# BOTTOM_BRD_v_1_0_4.net
KiCad netlist of a schematic drawn in EAGLE
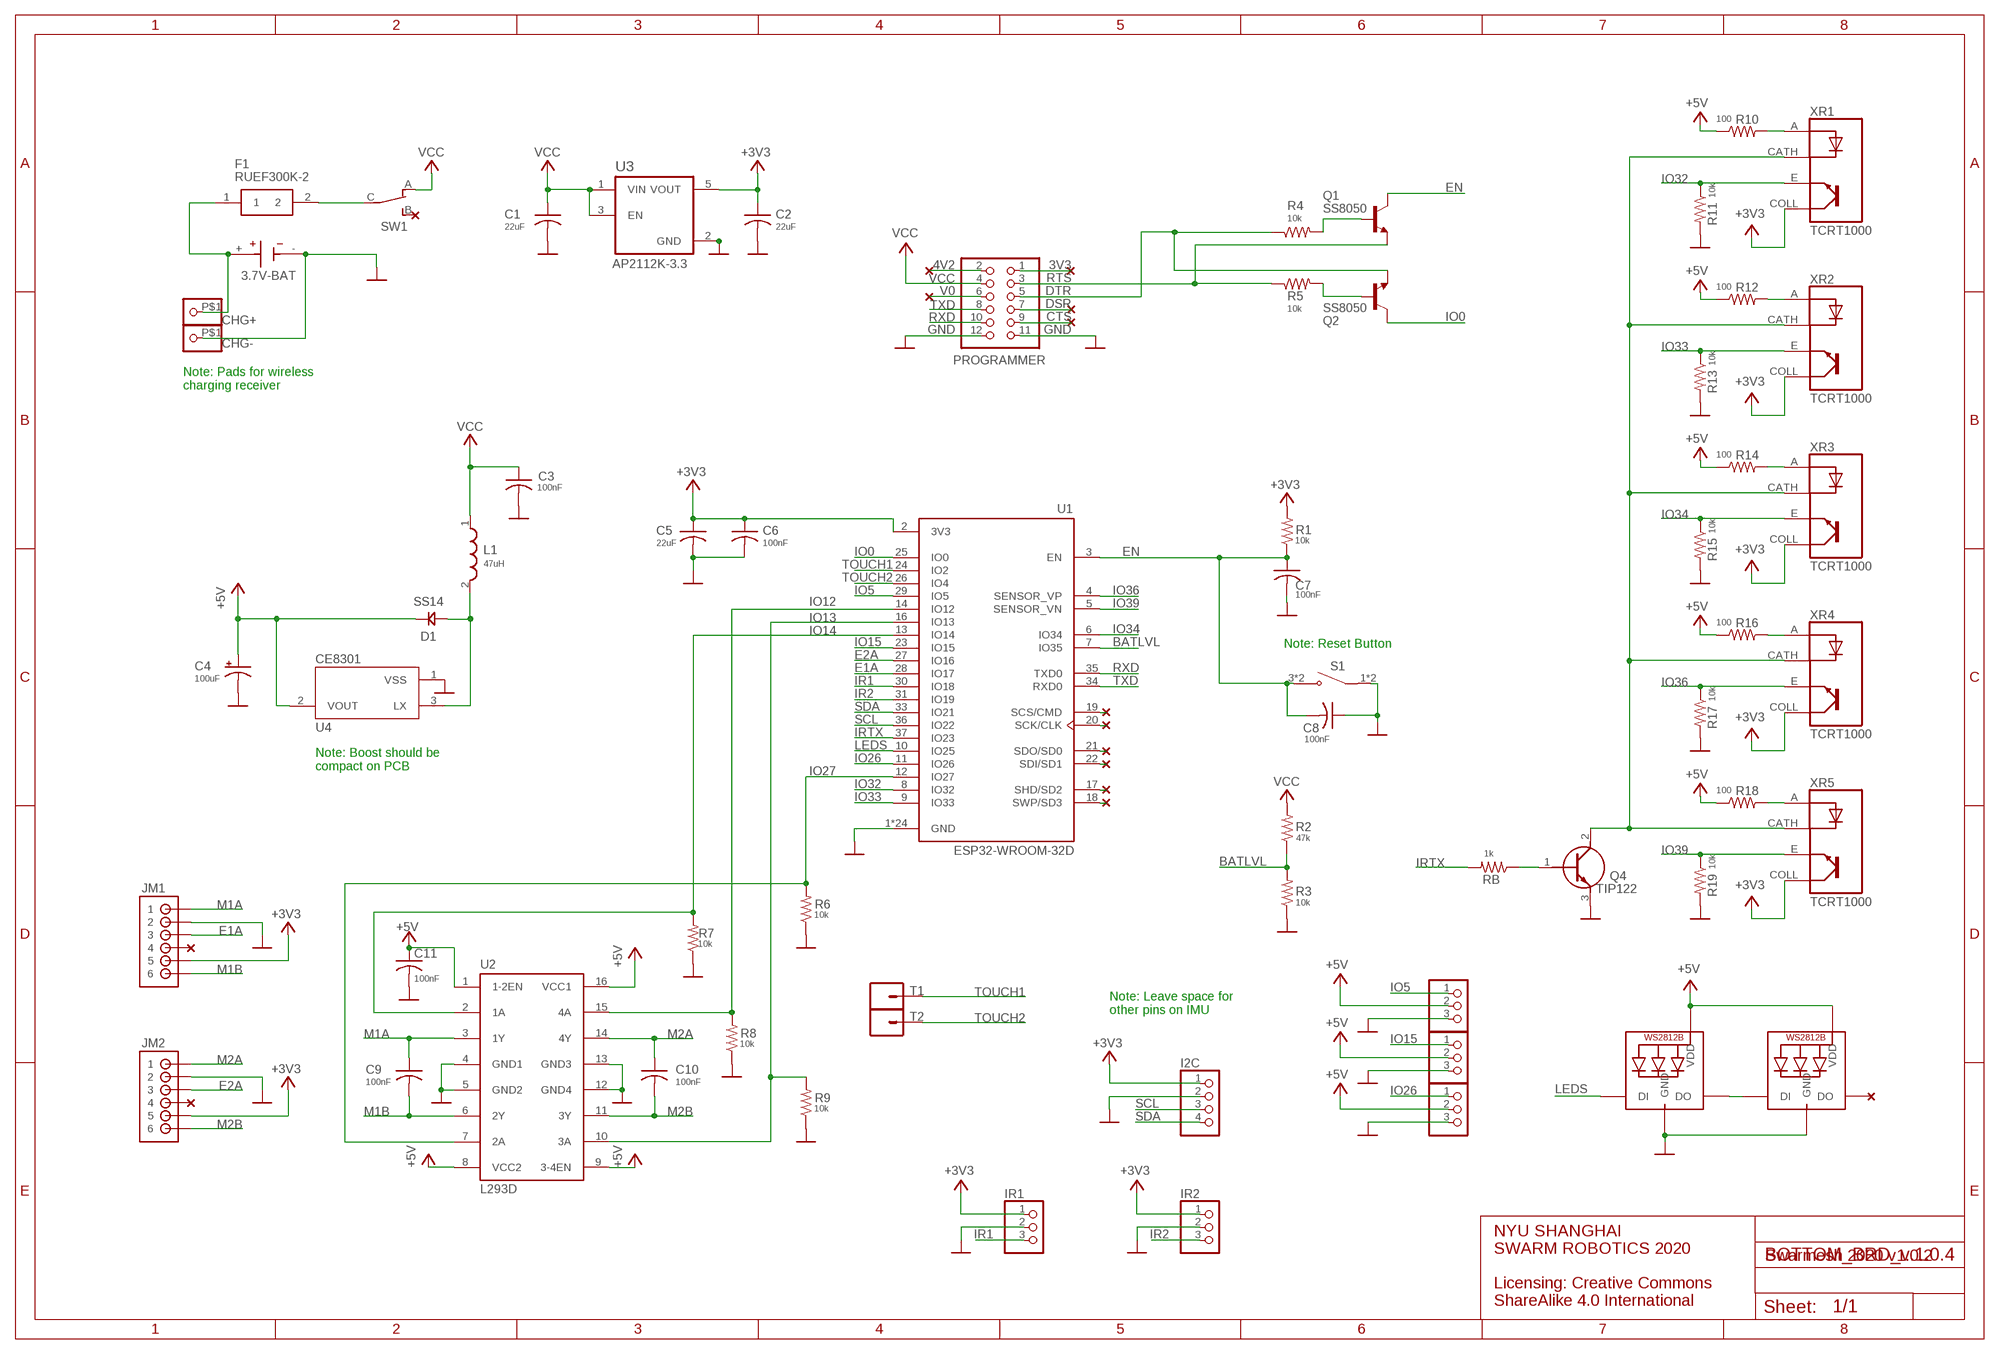
[diagram p0: schematic, sheet 1]

(export (version "E")
  (design (tool "Eeschema 10.0.6"))
  (components
    (comp (ref "BT")
      (value "3.7V-BAT")
      (footprint "eagle-import:BAT_6S-AA")
      (fields (field (name "MF") "MPD") (field (name "MP") "6S-AA"))
      (libsource (lib "eagle-import") (part "6S-AA"))
    )
    (comp (ref "C1")
      (value "22uF")
      (footprint "eagle-import:C0805")
      (libsource (lib "eagle-import") (part "C-USC0805"))
    )
    (comp (ref "C2")
      (value "22uF")
      (footprint "eagle-import:C0805")
      (libsource (lib "eagle-import") (part "C-USC0805"))
    )
    (comp (ref "C3")
      (value "100nF")
      (footprint "eagle-import:C0805")
      (libsource (lib "eagle-import") (part "C-USC0805"))
    )
    (comp (ref "C4")
      (value "100uF")
      (footprint "eagle-import:153CLV-0605")
      (libsource (lib "eagle-import") (part "CPOL-US153CLV-0605"))
    )
    (comp (ref "C5")
      (value "22uF")
      (footprint "eagle-import:C0805")
      (libsource (lib "eagle-import") (part "C-USC0805"))
    )
    (comp (ref "C6")
      (value "100nF")
      (footprint "eagle-import:C0805")
      (libsource (lib "eagle-import") (part "C-USC0805"))
    )
    (comp (ref "C7")
      (value "100nF")
      (footprint "eagle-import:C0805")
      (libsource (lib "eagle-import") (part "C-USC0805"))
    )
    (comp (ref "C8")
      (value "100nF")
      (footprint "eagle-import:C0805")
      (libsource (lib "eagle-import") (part "C-USC0805"))
    )
    (comp (ref "C9")
      (value "100nF")
      (footprint "eagle-import:C0805")
      (libsource (lib "eagle-import") (part "C-USC0805"))
    )
    (comp (ref "C10")
      (value "100nF")
      (footprint "eagle-import:C0805")
      (libsource (lib "eagle-import") (part "C-USC0805"))
    )
    (comp (ref "C11")
      (value "100nF")
      (footprint "eagle-import:C0805")
      (libsource (lib "eagle-import") (part "C-USC0805"))
    )
    (comp (ref "CHARGING")
      (value "WS2812B5050")
      (footprint "eagle-import:WS2812B")
      (libsource (lib "eagle-import") (part "WS2812B5050"))
    )
    (comp (ref "CHG+")
      (value "PINHD-1X1-BIGPOGO")
      (footprint "eagle-import:1X1-BIGPOGO")
      (libsource (lib "eagle-import") (part "PINHD-1X1-BIGPOGO"))
    )
    (comp (ref "CHG-")
      (value "PINHD-1X1-BIGPOGO")
      (footprint "eagle-import:1X1-BIGPOGO")
      (libsource (lib "eagle-import") (part "PINHD-1X1-BIGPOGO"))
    )
    (comp (ref "D1")
      (value "SS14")
      (footprint "eagle-import:DO214")
      (fields (field (name "MF") "ON Semiconductor"))
      (libsource (lib "eagle-import") (part "SS14"))
    )
    (comp (ref "F1")
      (value "RUEF300K-2")
      (footprint "eagle-import:RUEF300K2")
      (libsource (lib "eagle-import") (part "RUEF300K-2"))
    )
    (comp (ref "GPIO5")
      (value "PINHD-1X3")
      (footprint "eagle-import:1X03")
      (libsource (lib "eagle-import") (part "PINHD-1X3"))
    )
    (comp (ref "GPIO15")
      (value "PINHD-1X3")
      (footprint "eagle-import:1X03")
      (libsource (lib "eagle-import") (part "PINHD-1X3"))
    )
    (comp (ref "GPIO26")
      (value "PINHD-1X3")
      (footprint "eagle-import:1X03")
      (libsource (lib "eagle-import") (part "PINHD-1X3"))
    )
    (comp (ref "I2C")
      (value "PINHD-1X4")
      (footprint "eagle-import:1X04")
      (libsource (lib "eagle-import") (part "PINHD-1X4"))
    )
    (comp (ref "IR1")
      (value "PINHD-1X3")
      (footprint "eagle-import:1X03")
      (libsource (lib "eagle-import") (part "PINHD-1X3"))
    )
    (comp (ref "IR2")
      (value "PINHD-1X3")
      (footprint "eagle-import:1X03")
      (libsource (lib "eagle-import") (part "PINHD-1X3"))
    )
    (comp (ref "JM1")
      (value "B6B-ZR")
      (footprint "eagle-import:B6B-ZR")
      (fields (field (name "MF") "JST"))
      (libsource (lib "eagle-import") (part "B6B-ZR"))
    )
    (comp (ref "JM2")
      (value "B6B-ZR")
      (footprint "eagle-import:B6B-ZR")
      (fields (field (name "MF") "JST"))
      (libsource (lib "eagle-import") (part "B6B-ZR"))
    )
    (comp (ref "L1")
      (value "47uH")
      (footprint "eagle-import:INDP5858X480N")
      (fields (field (name "MF") "Bourns") (field (name "MP") "SDR0604-100KL"))
      (libsource (lib "eagle-import") (part "SDR0604-100KL"))
    )
    (comp (ref "PROGRAMMER")
      (value "PINHD-2X6")
      (footprint "eagle-import:2X06")
      (libsource (lib "eagle-import") (part "PINHD-2X6"))
    )
    (comp (ref "Q1")
      (value "SS8050")
      (footprint "eagle-import:SOT23")
      (libsource (lib "eagle-import") (part "BC850"))
    )
    (comp (ref "Q2")
      (value "SS8050")
      (footprint "eagle-import:SOT23")
      (libsource (lib "eagle-import") (part "BC850"))
    )
    (comp (ref "Q4")
      (value "TIP122")
      (footprint "eagle-import:TO270P460X1020X2008-3P")
      (fields (field (name "MOUSER_PART_NUMBER") "511-TIP122"))
      (libsource (lib "eagle-import") (part "TIP122"))
    )
    (comp (ref "R1")
      (value "10k")
      (footprint "eagle-import:M0805")
      (libsource (lib "eagle-import") (part "R-US_M0805"))
    )
    (comp (ref "R2")
      (value "47k")
      (footprint "eagle-import:M0805")
      (libsource (lib "eagle-import") (part "R-US_M0805"))
    )
    (comp (ref "R3")
      (value "10k")
      (footprint "eagle-import:M0805")
      (libsource (lib "eagle-import") (part "R-US_M0805"))
    )
    (comp (ref "R4")
      (value "10k")
      (footprint "eagle-import:M0805")
      (libsource (lib "eagle-import") (part "R-US_M0805"))
    )
    (comp (ref "R5")
      (value "10k")
      (footprint "eagle-import:M0805")
      (libsource (lib "eagle-import") (part "R-US_M0805"))
    )
    (comp (ref "R6")
      (value "10k")
      (footprint "eagle-import:M0805")
      (libsource (lib "eagle-import") (part "R-US_M0805"))
    )
    (comp (ref "R7")
      (value "10k")
      (footprint "eagle-import:M0805")
      (libsource (lib "eagle-import") (part "R-US_M0805"))
    )
    (comp (ref "R8")
      (value "10k")
      (footprint "eagle-import:M0805")
      (libsource (lib "eagle-import") (part "R-US_M0805"))
    )
    (comp (ref "R9")
      (value "10k")
      (footprint "eagle-import:M0805")
      (libsource (lib "eagle-import") (part "R-US_M0805"))
    )
    (comp (ref "R10")
      (value "100")
      (footprint "eagle-import:M0805")
      (libsource (lib "eagle-import") (part "R-US_M0805"))
    )
    (comp (ref "R11")
      (value "10k")
      (footprint "eagle-import:M0805")
      (libsource (lib "eagle-import") (part "R-US_M0805"))
    )
    (comp (ref "R12")
      (value "100")
      (footprint "eagle-import:M0805")
      (libsource (lib "eagle-import") (part "R-US_M0805"))
    )
    (comp (ref "R13")
      (value "10k")
      (footprint "eagle-import:M0805")
      (libsource (lib "eagle-import") (part "R-US_M0805"))
    )
    (comp (ref "R14")
      (value "100")
      (footprint "eagle-import:M0805")
      (libsource (lib "eagle-import") (part "R-US_M0805"))
    )
    (comp (ref "R15")
      (value "10k")
      (footprint "eagle-import:M0805")
      (libsource (lib "eagle-import") (part "R-US_M0805"))
    )
    (comp (ref "R16")
      (value "100")
      (footprint "eagle-import:M0805")
      (libsource (lib "eagle-import") (part "R-US_M0805"))
    )
    (comp (ref "R17")
      (value "10k")
      (footprint "eagle-import:M0805")
      (libsource (lib "eagle-import") (part "R-US_M0805"))
    )
    (comp (ref "R18")
      (value "100")
      (footprint "eagle-import:M0805")
      (libsource (lib "eagle-import") (part "R-US_M0805"))
    )
    (comp (ref "R19")
      (value "10k")
      (footprint "eagle-import:M0805")
      (libsource (lib "eagle-import") (part "R-US_M0805"))
    )
    (comp (ref "RB")
      (value "1k")
      (footprint "eagle-import:M0805")
      (libsource (lib "eagle-import") (part "R-US_M0805"))
    )
    (comp (ref "S1")
      (value "2-1437565-9")
      (footprint "eagle-import:SW_2-1437565-9")
      (fields (field (name "MF") "TE Connectivity"))
      (libsource (lib "eagle-import") (part "2-1437565-9"))
    )
    (comp (ref "STATE")
      (value "WS2812B5050")
      (footprint "eagle-import:WS2812B")
      (libsource (lib "eagle-import") (part "WS2812B5050"))
    )
    (comp (ref "SW1")
      (value "CS12ANW03")
      (footprint "eagle-import:CS12ANW03")
      (fields (field (name "MF") "NKK Switches"))
      (libsource (lib "eagle-import") (part "CS12ANW03"))
    )
    (comp (ref "T1")
      (value "CONN_01SPRING-CONN")
      (footprint "eagle-import:SPRING-CONNECTOR")
      (libsource (lib "eagle-import") (part "Touch_Pad2_CONN_01SPRING-CONN"))
    )
    (comp (ref "T2")
      (value "CONN_01SPRING-CONN")
      (footprint "eagle-import:SPRING-CONNECTOR")
      (libsource (lib "eagle-import") (part "CONN_01SPRING-CONN"))
    )
    (comp (ref "U1")
      (value "ESP32-WROOM-32D")
      (footprint "eagle-import:MODULE_ESP32-WROOM-32D")
      (fields (field (name "MF") "Espressif Systems"))
      (libsource (lib "eagle-import") (part "ESP32-WROOM-32D"))
    )
    (comp (ref "U2")
      (value "L293D")
      (footprint "eagle-import:DIL16")
      (libsource (lib "eagle-import") (part "L293D"))
    )
    (comp (ref "U3")
      (value "AP2112K-3.3")
      (footprint "eagle-import:SOT95P285X140-5N")
      (fields (field (name "MF") "Diodes Inc.") (field (name "MP") "AP2112K-3.3TRG1"))
      (libsource (lib "eagle-import") (part "AP2112K-3.3TRG1"))
    )
    (comp (ref "U4")
      (value "CE8301")
      (footprint "eagle-import:REG_MCP1702T-3302E_MB")
      (fields (field (name "MF") "Microchip") (field (name "MP") "MCP1702T-3302E/MB"))
      (libsource (lib "eagle-import") (part "MCP1702T-3302E/MB"))
    )
    (comp (ref "XR1")
      (value "TCRT1000")
      (footprint "eagle-import:XDCR_TCRT1000")
      (fields (field (name "MF") "Vishay"))
      (libsource (lib "eagle-import") (part "TCRT1000"))
    )
    (comp (ref "XR2")
      (value "TCRT1000")
      (footprint "eagle-import:XDCR_TCRT1000")
      (fields (field (name "MF") "Vishay"))
      (libsource (lib "eagle-import") (part "TCRT1000"))
    )
    (comp (ref "XR3")
      (value "TCRT1000")
      (footprint "eagle-import:XDCR_TCRT1000")
      (fields (field (name "MF") "Vishay"))
      (libsource (lib "eagle-import") (part "TCRT1000"))
    )
    (comp (ref "XR4")
      (value "TCRT1000")
      (footprint "eagle-import:XDCR_TCRT1000")
      (fields (field (name "MF") "Vishay"))
      (libsource (lib "eagle-import") (part "TCRT1000"))
    )
    (comp (ref "XR5")
      (value "TCRT1000")
      (footprint "eagle-import:XDCR_TCRT1000")
      (fields (field (name "MF") "Vishay"))
      (libsource (lib "eagle-import") (part "TCRT1000"))
    )
  )
  (nets
    (net (code "1") (name "+3V3") (class "Default")
      (node (ref "C2") (pin "1") (pinfunction "1_1") (pintype "passive"))
      (node (ref "C5") (pin "1") (pinfunction "1_1") (pintype "passive"))
      (node (ref "C6") (pin "1") (pinfunction "1_1") (pintype "passive"))
      (node (ref "I2C") (pin "1") (pinfunction "1_1") (pintype "passive"))
      (node (ref "IR1") (pin "1") (pinfunction "1_1") (pintype "passive"))
      (node (ref "IR2") (pin "1") (pinfunction "1_1") (pintype "passive"))
      (node (ref "JM1") (pin "5") (pinfunction "5_5") (pintype "bidirectional"))
      (node (ref "JM2") (pin "5") (pinfunction "5_5") (pintype "bidirectional"))
      (node (ref "R1") (pin "2") (pinfunction "2_2") (pintype "passive"))
      (node (ref "U1") (pin "2") (pinfunction "3V3_2") (pintype "power_in"))
      (node (ref "U3") (pin "5") (pinfunction "VOUT_5") (pintype "power_in"))
      (node (ref "XR1") (pin "COLL") (pinfunction "CO_COLL") (pintype "passive"))
      (node (ref "XR2") (pin "COLL") (pinfunction "CO_COLL") (pintype "passive"))
      (node (ref "XR3") (pin "COLL") (pinfunction "CO_COLL") (pintype "passive"))
      (node (ref "XR4") (pin "COLL") (pinfunction "CO_COLL") (pintype "passive"))
      (node (ref "XR5") (pin "COLL") (pinfunction "CO_COLL") (pintype "passive"))
    )
    (net (code "2") (name "+5V") (class "Default")
      (node (ref "C11") (pin "1") (pinfunction "1_1") (pintype "passive"))
      (node (ref "C4") (pin "+") (pinfunction "+_+") (pintype "passive"))
      (node (ref "CHARGING") (pin "1-VDD") (pinfunction "VDD_1-VDD") (pintype "power_in"))
      (node (ref "D1") (pin "CATHODE") (pinfunction "KATHODE_CATHODE") (pintype "bidirectional"))
      (node (ref "GPIO15") (pin "2") (pinfunction "2_2") (pintype "passive"))
      (node (ref "GPIO26") (pin "2") (pinfunction "2_2") (pintype "passive"))
      (node (ref "GPIO5") (pin "2") (pinfunction "2_2") (pintype "passive"))
      (node (ref "R10") (pin "1") (pinfunction "1_1") (pintype "passive"))
      (node (ref "R12") (pin "1") (pinfunction "1_1") (pintype "passive"))
      (node (ref "R14") (pin "1") (pinfunction "1_1") (pintype "passive"))
      (node (ref "R16") (pin "1") (pinfunction "1_1") (pintype "passive"))
      (node (ref "R18") (pin "1") (pinfunction "1_1") (pintype "passive"))
      (node (ref "STATE") (pin "1-VDD") (pinfunction "VDD_1-VDD") (pintype "power_in"))
      (node (ref "U2") (pin "1") (pinfunction "1-2EN_1") (pintype "input"))
      (node (ref "U2") (pin "16") (pinfunction "VCC1_16") (pintype "power_in"))
      (node (ref "U2") (pin "8") (pinfunction "VCC2_8") (pintype "power_in"))
      (node (ref "U2") (pin "9") (pinfunction "3-4EN_9") (pintype "input"))
      (node (ref "U4") (pin "2") (pinfunction "VOUT_2") (pintype "input"))
    )
    (net (code "3") (name "/3V3") (class "Default")
      (node (ref "PROGRAMMER") (pin "1") (pinfunction "1_1") (pintype "passive"))
    )
    (net (code "4") (name "/4V2") (class "Default")
      (node (ref "PROGRAMMER") (pin "2") (pinfunction "2_2") (pintype "passive"))
    )
    (net (code "5") (name "/BATLVL") (class "Default")
      (node (ref "R2") (pin "1") (pinfunction "1_1") (pintype "passive"))
      (node (ref "R3") (pin "2") (pinfunction "2_2") (pintype "passive"))
      (node (ref "U1") (pin "7") (pinfunction "IO35_7") (pintype "input"))
    )
    (net (code "6") (name "/CTS") (class "Default")
      (node (ref "PROGRAMMER") (pin "9") (pinfunction "9_9") (pintype "passive"))
    )
    (net (code "7") (name "/DSR") (class "Default")
      (node (ref "PROGRAMMER") (pin "7") (pinfunction "7_7") (pintype "passive"))
    )
    (net (code "8") (name "/DTR") (class "Default")
      (node (ref "PROGRAMMER") (pin "5") (pinfunction "5_5") (pintype "passive"))
      (node (ref "Q2") (pin "2") (pinfunction "E_2") (pintype "passive"))
      (node (ref "R4") (pin "1") (pinfunction "1_1") (pintype "passive"))
    )
    (net (code "9") (name "/E1A") (class "Default")
      (node (ref "JM1") (pin "3") (pinfunction "3_3") (pintype "bidirectional"))
      (node (ref "U1") (pin "28") (pinfunction "IO17_28") (pintype "bidirectional"))
    )
    (net (code "10") (name "/E2A") (class "Default")
      (node (ref "JM2") (pin "3") (pinfunction "3_3") (pintype "bidirectional"))
      (node (ref "U1") (pin "27") (pinfunction "IO16_27") (pintype "bidirectional"))
    )
    (net (code "11") (name "/EN") (class "Default")
      (node (ref "C7") (pin "1") (pinfunction "1_1") (pintype "passive"))
      (node (ref "C8") (pin "2") (pinfunction "2_2") (pintype "passive"))
      (node (ref "Q1") (pin "3") (pinfunction "C_3") (pintype "passive"))
      (node (ref "R1") (pin "1") (pinfunction "1_1") (pintype "passive"))
      (node (ref "S1") (pin "3") (pinfunction "NO_3") (pintype "passive"))
      (node (ref "S1") (pin "4") (pinfunction "NO_4") (pintype "passive"))
      (node (ref "U1") (pin "3") (pinfunction "EN_3") (pintype "input"))
    )
    (net (code "12") (name "/IO0") (class "Default")
      (node (ref "Q2") (pin "3") (pinfunction "C_3") (pintype "passive"))
      (node (ref "U1") (pin "25") (pinfunction "IO0_25") (pintype "bidirectional"))
    )
    (net (code "13") (name "/IO5") (class "Default")
      (node (ref "GPIO5") (pin "1") (pinfunction "1_1") (pintype "passive"))
      (node (ref "U1") (pin "29") (pinfunction "IO5_29") (pintype "bidirectional"))
    )
    (net (code "14") (name "/IO12") (class "Default")
      (node (ref "R8") (pin "2") (pinfunction "2_2") (pintype "passive"))
      (node (ref "U1") (pin "14") (pinfunction "IO12_14") (pintype "bidirectional"))
      (node (ref "U2") (pin "15") (pinfunction "4A_15") (pintype "input"))
    )
    (net (code "15") (name "/IO13") (class "Default")
      (node (ref "R9") (pin "2") (pinfunction "2_2") (pintype "passive"))
      (node (ref "U1") (pin "16") (pinfunction "IO13_16") (pintype "bidirectional"))
      (node (ref "U2") (pin "10") (pinfunction "3A_10") (pintype "input"))
    )
    (net (code "16") (name "/IO14") (class "Default")
      (node (ref "R7") (pin "2") (pinfunction "2_2") (pintype "passive"))
      (node (ref "U1") (pin "13") (pinfunction "IO14_13") (pintype "bidirectional"))
      (node (ref "U2") (pin "2") (pinfunction "1A_2") (pintype "input"))
    )
    (net (code "17") (name "/IO15") (class "Default")
      (node (ref "GPIO15") (pin "1") (pinfunction "1_1") (pintype "passive"))
      (node (ref "U1") (pin "23") (pinfunction "IO15_23") (pintype "bidirectional"))
    )
    (net (code "18") (name "/IO26") (class "Default")
      (node (ref "GPIO26") (pin "1") (pinfunction "1_1") (pintype "passive"))
      (node (ref "U1") (pin "11") (pinfunction "IO26_11") (pintype "bidirectional"))
    )
    (net (code "19") (name "/IO27") (class "Default")
      (node (ref "R6") (pin "2") (pinfunction "2_2") (pintype "passive"))
      (node (ref "U1") (pin "12") (pinfunction "IO27_12") (pintype "bidirectional"))
      (node (ref "U2") (pin "7") (pinfunction "2A_7") (pintype "input"))
    )
    (net (code "20") (name "/IO32") (class "Default")
      (node (ref "R11") (pin "1") (pinfunction "1_1") (pintype "passive"))
      (node (ref "U1") (pin "8") (pinfunction "IO32_8") (pintype "bidirectional"))
      (node (ref "XR1") (pin "E") (pinfunction "E_E") (pintype "passive"))
    )
    (net (code "21") (name "/IO33") (class "Default")
      (node (ref "R13") (pin "1") (pinfunction "1_1") (pintype "passive"))
      (node (ref "U1") (pin "9") (pinfunction "IO33_9") (pintype "bidirectional"))
      (node (ref "XR2") (pin "E") (pinfunction "E_E") (pintype "passive"))
    )
    (net (code "22") (name "/IO34") (class "Default")
      (node (ref "R15") (pin "1") (pinfunction "1_1") (pintype "passive"))
      (node (ref "U1") (pin "6") (pinfunction "IO34_6") (pintype "input"))
      (node (ref "XR3") (pin "E") (pinfunction "E_E") (pintype "passive"))
    )
    (net (code "23") (name "/IO36") (class "Default")
      (node (ref "R17") (pin "1") (pinfunction "1_1") (pintype "passive"))
      (node (ref "U1") (pin "4") (pinfunction "SENSOR_VP_4") (pintype "input"))
      (node (ref "XR4") (pin "E") (pinfunction "E_E") (pintype "passive"))
    )
    (net (code "24") (name "/IO39") (class "Default")
      (node (ref "R19") (pin "1") (pinfunction "1_1") (pintype "passive"))
      (node (ref "U1") (pin "5") (pinfunction "SENSOR_VN_5") (pintype "input"))
      (node (ref "XR5") (pin "E") (pinfunction "E_E") (pintype "passive"))
    )
    (net (code "25") (name "/IR1") (class "Default")
      (node (ref "IR1") (pin "3") (pinfunction "3_3") (pintype "passive"))
      (node (ref "U1") (pin "30") (pinfunction "IO18_30") (pintype "bidirectional"))
    )
    (net (code "26") (name "/IR2") (class "Default")
      (node (ref "IR2") (pin "3") (pinfunction "3_3") (pintype "passive"))
      (node (ref "U1") (pin "31") (pinfunction "IO19_31") (pintype "bidirectional"))
    )
    (net (code "27") (name "/IRTX") (class "Default")
      (node (ref "RB") (pin "2") (pinfunction "2_2") (pintype "passive"))
      (node (ref "U1") (pin "37") (pinfunction "IO23_37") (pintype "bidirectional"))
    )
    (net (code "28") (name "/LEDS") (class "Default")
      (node (ref "CHARGING") (pin "4-DIN") (pinfunction "DI_4-DIN") (pintype "input"))
      (node (ref "U1") (pin "10") (pinfunction "IO25_10") (pintype "bidirectional"))
    )
    (net (code "29") (name "/M1A") (class "Default")
      (node (ref "C9") (pin "1") (pinfunction "1_1") (pintype "passive"))
      (node (ref "JM1") (pin "1") (pinfunction "1_1") (pintype "bidirectional"))
      (node (ref "U2") (pin "3") (pinfunction "1Y_3") (pintype "output"))
    )
    (net (code "30") (name "/M1B") (class "Default")
      (node (ref "C9") (pin "2") (pinfunction "2_2") (pintype "passive"))
      (node (ref "JM1") (pin "6") (pinfunction "6_6") (pintype "bidirectional"))
      (node (ref "U2") (pin "6") (pinfunction "2Y_6") (pintype "output"))
    )
    (net (code "31") (name "/M2A") (class "Default")
      (node (ref "C10") (pin "1") (pinfunction "1_1") (pintype "passive"))
      (node (ref "JM2") (pin "1") (pinfunction "1_1") (pintype "bidirectional"))
      (node (ref "U2") (pin "14") (pinfunction "4Y_14") (pintype "output"))
    )
    (net (code "32") (name "/M2B") (class "Default")
      (node (ref "C10") (pin "2") (pinfunction "2_2") (pintype "passive"))
      (node (ref "JM2") (pin "6") (pinfunction "6_6") (pintype "bidirectional"))
      (node (ref "U2") (pin "11") (pinfunction "3Y_11") (pintype "output"))
    )
    (net (code "33") (name "/RTS") (class "Default")
      (node (ref "PROGRAMMER") (pin "3") (pinfunction "3_3") (pintype "passive"))
      (node (ref "Q1") (pin "2") (pinfunction "E_2") (pintype "passive"))
      (node (ref "R5") (pin "1") (pinfunction "1_1") (pintype "passive"))
    )
    (net (code "34") (name "/RXD") (class "Default")
      (node (ref "PROGRAMMER") (pin "10") (pinfunction "10_10") (pintype "passive"))
      (node (ref "U1") (pin "35") (pinfunction "TXD0_35") (pintype "bidirectional"))
    )
    (net (code "35") (name "/SCL") (class "Default")
      (node (ref "I2C") (pin "3") (pinfunction "3_3") (pintype "passive"))
      (node (ref "U1") (pin "36") (pinfunction "IO22_36") (pintype "bidirectional"))
    )
    (net (code "36") (name "/SDA") (class "Default")
      (node (ref "I2C") (pin "4") (pinfunction "4_4") (pintype "passive"))
      (node (ref "U1") (pin "33") (pinfunction "IO21_33") (pintype "bidirectional"))
    )
    (net (code "37") (name "/TOUCH1") (class "Default")
      (node (ref "T1") (pin "P$2") (pinfunction "1_P$2") (pintype "passive"))
      (node (ref "U1") (pin "24") (pinfunction "IO2_24") (pintype "bidirectional"))
    )
    (net (code "38") (name "/TOUCH2") (class "Default")
      (node (ref "T2") (pin "P$2") (pinfunction "1_P$2") (pintype "passive"))
      (node (ref "U1") (pin "26") (pinfunction "IO4_26") (pintype "bidirectional"))
    )
    (net (code "39") (name "/TXD") (class "Default")
      (node (ref "PROGRAMMER") (pin "8") (pinfunction "8_8") (pintype "passive"))
      (node (ref "U1") (pin "34") (pinfunction "RXD0_34") (pintype "bidirectional"))
    )
    (net (code "40") (name "/V0") (class "Default")
      (node (ref "PROGRAMMER") (pin "6") (pinfunction "6_6") (pintype "passive"))
    )
    (net (code "41") (name "GND") (class "Default")
      (node (ref "BT") (pin "-") (pinfunction "-_-") (pintype "passive"))
      (node (ref "C1") (pin "2") (pinfunction "2_2") (pintype "passive"))
      (node (ref "C11") (pin "2") (pinfunction "2_2") (pintype "passive"))
      (node (ref "C2") (pin "2") (pinfunction "2_2") (pintype "passive"))
      (node (ref "C3") (pin "2") (pinfunction "2_2") (pintype "passive"))
      (node (ref "C4") (pin "-") (pinfunction "-_-") (pintype "passive"))
      (node (ref "C5") (pin "2") (pinfunction "2_2") (pintype "passive"))
      (node (ref "C6") (pin "2") (pinfunction "2_2") (pintype "passive"))
      (node (ref "C7") (pin "2") (pinfunction "2_2") (pintype "passive"))
      (node (ref "C8") (pin "1") (pinfunction "1_1") (pintype "passive"))
      (node (ref "CHARGING") (pin "3-GND") (pinfunction "GND_3-GND") (pintype "power_in"))
      (node (ref "CHG-") (pin "P$1") (pinfunction "1_P$1") (pintype "passive"))
      (node (ref "GPIO15") (pin "3") (pinfunction "3_3") (pintype "passive"))
      (node (ref "GPIO26") (pin "3") (pinfunction "3_3") (pintype "passive"))
      (node (ref "GPIO5") (pin "3") (pinfunction "3_3") (pintype "passive"))
      (node (ref "I2C") (pin "2") (pinfunction "2_2") (pintype "passive"))
      (node (ref "IR1") (pin "2") (pinfunction "2_2") (pintype "passive"))
      (node (ref "IR2") (pin "2") (pinfunction "2_2") (pintype "passive"))
      (node (ref "JM1") (pin "2") (pinfunction "2_2") (pintype "bidirectional"))
      (node (ref "JM2") (pin "2") (pinfunction "2_2") (pintype "bidirectional"))
      (node (ref "PROGRAMMER") (pin "11") (pinfunction "11_11") (pintype "passive"))
      (node (ref "PROGRAMMER") (pin "12") (pinfunction "12_12") (pintype "passive"))
      (node (ref "Q4") (pin "3") (pinfunction "E_3") (pintype "bidirectional"))
      (node (ref "R11") (pin "2") (pinfunction "2_2") (pintype "passive"))
      (node (ref "R13") (pin "2") (pinfunction "2_2") (pintype "passive"))
      (node (ref "R15") (pin "2") (pinfunction "2_2") (pintype "passive"))
      (node (ref "R17") (pin "2") (pinfunction "2_2") (pintype "passive"))
      (node (ref "R19") (pin "2") (pinfunction "2_2") (pintype "passive"))
      (node (ref "R3") (pin "1") (pinfunction "1_1") (pintype "passive"))
      (node (ref "R6") (pin "1") (pinfunction "1_1") (pintype "passive"))
      (node (ref "R7") (pin "1") (pinfunction "1_1") (pintype "passive"))
      (node (ref "R8") (pin "1") (pinfunction "1_1") (pintype "passive"))
      (node (ref "R9") (pin "1") (pinfunction "1_1") (pintype "passive"))
      (node (ref "S1") (pin "1") (pinfunction "COM_1") (pintype "passive"))
      (node (ref "S1") (pin "2") (pinfunction "COM_2") (pintype "passive"))
      (node (ref "STATE") (pin "3-GND") (pinfunction "GND_3-GND") (pintype "power_in"))
      (node (ref "U1") (pin "1") (pinfunction "GND_1") (pintype "power_in"))
      (node (ref "U1") (pin "15") (pinfunction "GND_15") (pintype "power_in"))
      (node (ref "U1") (pin "38") (pinfunction "GND_38") (pintype "power_in"))
      (node (ref "U1") (pin "39_1") (pinfunction "GND_39_1") (pintype "power_in"))
      (node (ref "U1") (pin "39_10") (pinfunction "GND_39_10") (pintype "power_in"))
      (node (ref "U1") (pin "39_11") (pinfunction "GND_39_11") (pintype "power_in"))
      (node (ref "U1") (pin "39_12") (pinfunction "GND_39_12") (pintype "power_in"))
      (node (ref "U1") (pin "39_13") (pinfunction "GND_39_13") (pintype "power_in"))
      (node (ref "U1") (pin "39_14") (pinfunction "GND_39_14") (pintype "power_in"))
      (node (ref "U1") (pin "39_15") (pinfunction "GND_39_15") (pintype "power_in"))
      (node (ref "U1") (pin "39_16") (pinfunction "GND_39_16") (pintype "power_in"))
      (node (ref "U1") (pin "39_17") (pinfunction "GND_39_17") (pintype "power_in"))
      (node (ref "U1") (pin "39_18") (pinfunction "GND_39_18") (pintype "power_in"))
      (node (ref "U1") (pin "39_19") (pinfunction "GND_39_19") (pintype "power_in"))
      (node (ref "U1") (pin "39_2") (pinfunction "GND_39_2") (pintype "power_in"))
      (node (ref "U1") (pin "39_20") (pinfunction "GND_39_20") (pintype "power_in"))
      (node (ref "U1") (pin "39_21") (pinfunction "GND_39_21") (pintype "power_in"))
      (node (ref "U1") (pin "39_3") (pinfunction "GND_39_3") (pintype "power_in"))
      (node (ref "U1") (pin "39_4") (pinfunction "GND_39_4") (pintype "power_in"))
      (node (ref "U1") (pin "39_5") (pinfunction "GND_39_5") (pintype "power_in"))
      (node (ref "U1") (pin "39_6") (pinfunction "GND_39_6") (pintype "power_in"))
      (node (ref "U1") (pin "39_7") (pinfunction "GND_39_7") (pintype "power_in"))
      (node (ref "U1") (pin "39_8") (pinfunction "GND_39_8") (pintype "power_in"))
      (node (ref "U1") (pin "39_9") (pinfunction "GND_39_9") (pintype "power_in"))
      (node (ref "U2") (pin "12") (pinfunction "GND4_12") (pintype "power_in"))
      (node (ref "U2") (pin "13") (pinfunction "GND3_13") (pintype "power_in"))
      (node (ref "U2") (pin "4") (pinfunction "GND1_4") (pintype "power_in"))
      (node (ref "U2") (pin "5") (pinfunction "GND2_5") (pintype "power_in"))
      (node (ref "U3") (pin "2") (pinfunction "GND_2") (pintype "power_in"))
      (node (ref "U4") (pin "1") (pinfunction "VSS_1") (pintype "power_in"))
    )
    (net (code "42") (name "Net-(CHARGING-DO)") (class "Default")
      (node (ref "CHARGING") (pin "2-DOUT") (pinfunction "DO_2-DOUT") (pintype "output"))
      (node (ref "STATE") (pin "4-DIN") (pinfunction "DI_4-DIN") (pintype "input"))
    )
    (net (code "43") (name "Net-(CHG+-1)") (class "Default")
      (node (ref "BT") (pin "+") (pinfunction "+_+") (pintype "passive"))
      (node (ref "CHG+") (pin "P$1") (pinfunction "1_P$1") (pintype "passive"))
      (node (ref "F1") (pin "1") (pinfunction "1_1") (pintype "bidirectional"))
    )
    (net (code "44") (name "Net-(F1-Pad2)") (class "Default")
      (node (ref "F1") (pin "2") (pinfunction "2_2") (pintype "bidirectional"))
      (node (ref "SW1") (pin "C") (pinfunction "C_C") (pintype "passive"))
    )
    (net (code "45") (name "Net-(Q1-B)") (class "Default")
      (node (ref "Q1") (pin "1") (pinfunction "B_1") (pintype "passive"))
      (node (ref "R4") (pin "2") (pinfunction "2_2") (pintype "passive"))
    )
    (net (code "46") (name "Net-(Q2-B)") (class "Default")
      (node (ref "Q2") (pin "1") (pinfunction "B_1") (pintype "passive"))
      (node (ref "R5") (pin "2") (pinfunction "2_2") (pintype "passive"))
    )
    (net (code "47") (name "Net-(Q4-B)") (class "Default")
      (node (ref "Q4") (pin "1") (pinfunction "B_1") (pintype "bidirectional"))
      (node (ref "RB") (pin "1") (pinfunction "1_1") (pintype "passive"))
    )
    (net (code "48") (name "Net-(Q4-C)") (class "Default")
      (node (ref "Q4") (pin "2") (pinfunction "C_2") (pintype "bidirectional"))
      (node (ref "XR1") (pin "CATH") (pinfunction "C_CATH") (pintype "passive"))
      (node (ref "XR2") (pin "CATH") (pinfunction "C_CATH") (pintype "passive"))
      (node (ref "XR3") (pin "CATH") (pinfunction "C_CATH") (pintype "passive"))
      (node (ref "XR4") (pin "CATH") (pinfunction "C_CATH") (pintype "passive"))
      (node (ref "XR5") (pin "CATH") (pinfunction "C_CATH") (pintype "passive"))
    )
    (net (code "49") (name "Net-(R10-Pad2)") (class "Default")
      (node (ref "R10") (pin "2") (pinfunction "2_2") (pintype "passive"))
      (node (ref "XR1") (pin "A") (pinfunction "A_A") (pintype "passive"))
    )
    (net (code "50") (name "Net-(R12-Pad2)") (class "Default")
      (node (ref "R12") (pin "2") (pinfunction "2_2") (pintype "passive"))
      (node (ref "XR2") (pin "A") (pinfunction "A_A") (pintype "passive"))
    )
    (net (code "51") (name "Net-(R14-Pad2)") (class "Default")
      (node (ref "R14") (pin "2") (pinfunction "2_2") (pintype "passive"))
      (node (ref "XR3") (pin "A") (pinfunction "A_A") (pintype "passive"))
    )
    (net (code "52") (name "Net-(R16-Pad2)") (class "Default")
      (node (ref "R16") (pin "2") (pinfunction "2_2") (pintype "passive"))
      (node (ref "XR4") (pin "A") (pinfunction "A_A") (pintype "passive"))
    )
    (net (code "53") (name "Net-(R18-Pad2)") (class "Default")
      (node (ref "R18") (pin "2") (pinfunction "2_2") (pintype "passive"))
      (node (ref "XR5") (pin "A") (pinfunction "A_A") (pintype "passive"))
    )
    (net (code "54") (name "Net-(U4-LX)") (class "Default")
      (node (ref "D1") (pin "ANODE") (pinfunction "ANODE_ANODE") (pintype "bidirectional"))
      (node (ref "L1") (pin "2") (pinfunction "2_2") (pintype "passive"))
      (node (ref "U4") (pin "3") (pinfunction "LX_3") (pintype "output"))
    )
    (net (code "55") (name "VCC") (class "Default")
      (node (ref "C1") (pin "1") (pinfunction "1_1") (pintype "passive"))
      (node (ref "C3") (pin "1") (pinfunction "1_1") (pintype "passive"))
      (node (ref "L1") (pin "1") (pinfunction "1_1") (pintype "passive"))
      (node (ref "PROGRAMMER") (pin "4") (pinfunction "4_4") (pintype "passive"))
      (node (ref "R2") (pin "2") (pinfunction "2_2") (pintype "passive"))
      (node (ref "SW1") (pin "A") (pinfunction "A_A") (pintype "passive"))
      (node (ref "U3") (pin "1") (pinfunction "VIN_1") (pintype "power_in"))
      (node (ref "U3") (pin "3") (pinfunction "EN_3") (pintype "input"))
    )
    (net (code "56") (name "unconnected-(JM1-Pad4)") (class "Default")
      (node (ref "JM1") (pin "4") (pinfunction "4_4") (pintype "bidirectional"))
    )
    (net (code "57") (name "unconnected-(JM2-Pad4)") (class "Default")
      (node (ref "JM2") (pin "4") (pinfunction "4_4") (pintype "bidirectional"))
    )
    (net (code "58") (name "unconnected-(STATE-DO-Pad2-DOUT)") (class "Default")
      (node (ref "STATE") (pin "2-DOUT") (pinfunction "DO_2-DOUT") (pintype "output"))
    )
    (net (code "59") (name "unconnected-(SW1-PadB)") (class "Default")
      (node (ref "SW1") (pin "B") (pinfunction "B_B") (pintype "passive"))
    )
    (net (code "60") (name "unconnected-(U1-SCK{slash}CLK-Pad20)") (class "Default")
      (node (ref "U1") (pin "20") (pinfunction "SCK/CLK_20") (pintype "bidirectional"))
    )
    (net (code "61") (name "unconnected-(U1-SCS{slash}CMD-Pad19)") (class "Default")
      (node (ref "U1") (pin "19") (pinfunction "SCS/CMD_19") (pintype "bidirectional"))
    )
    (net (code "62") (name "unconnected-(U1-SDI{slash}SD1-Pad22)") (class "Default")
      (node (ref "U1") (pin "22") (pinfunction "SDI/SD1_22") (pintype "bidirectional"))
    )
    (net (code "63") (name "unconnected-(U1-SDO{slash}SD0-Pad21)") (class "Default")
      (node (ref "U1") (pin "21") (pinfunction "SDO/SD0_21") (pintype "bidirectional"))
    )
    (net (code "64") (name "unconnected-(U1-SHD{slash}SD2-Pad17)") (class "Default")
      (node (ref "U1") (pin "17") (pinfunction "SHD/SD2_17") (pintype "bidirectional"))
    )
    (net (code "65") (name "unconnected-(U1-SWP{slash}SD3-Pad18)") (class "Default")
      (node (ref "U1") (pin "18") (pinfunction "SWP/SD3_18") (pintype "bidirectional"))
    )
  )
)
